# 2_FPGA.net
KiCad netlist of a schematic drawn in Altium Designer
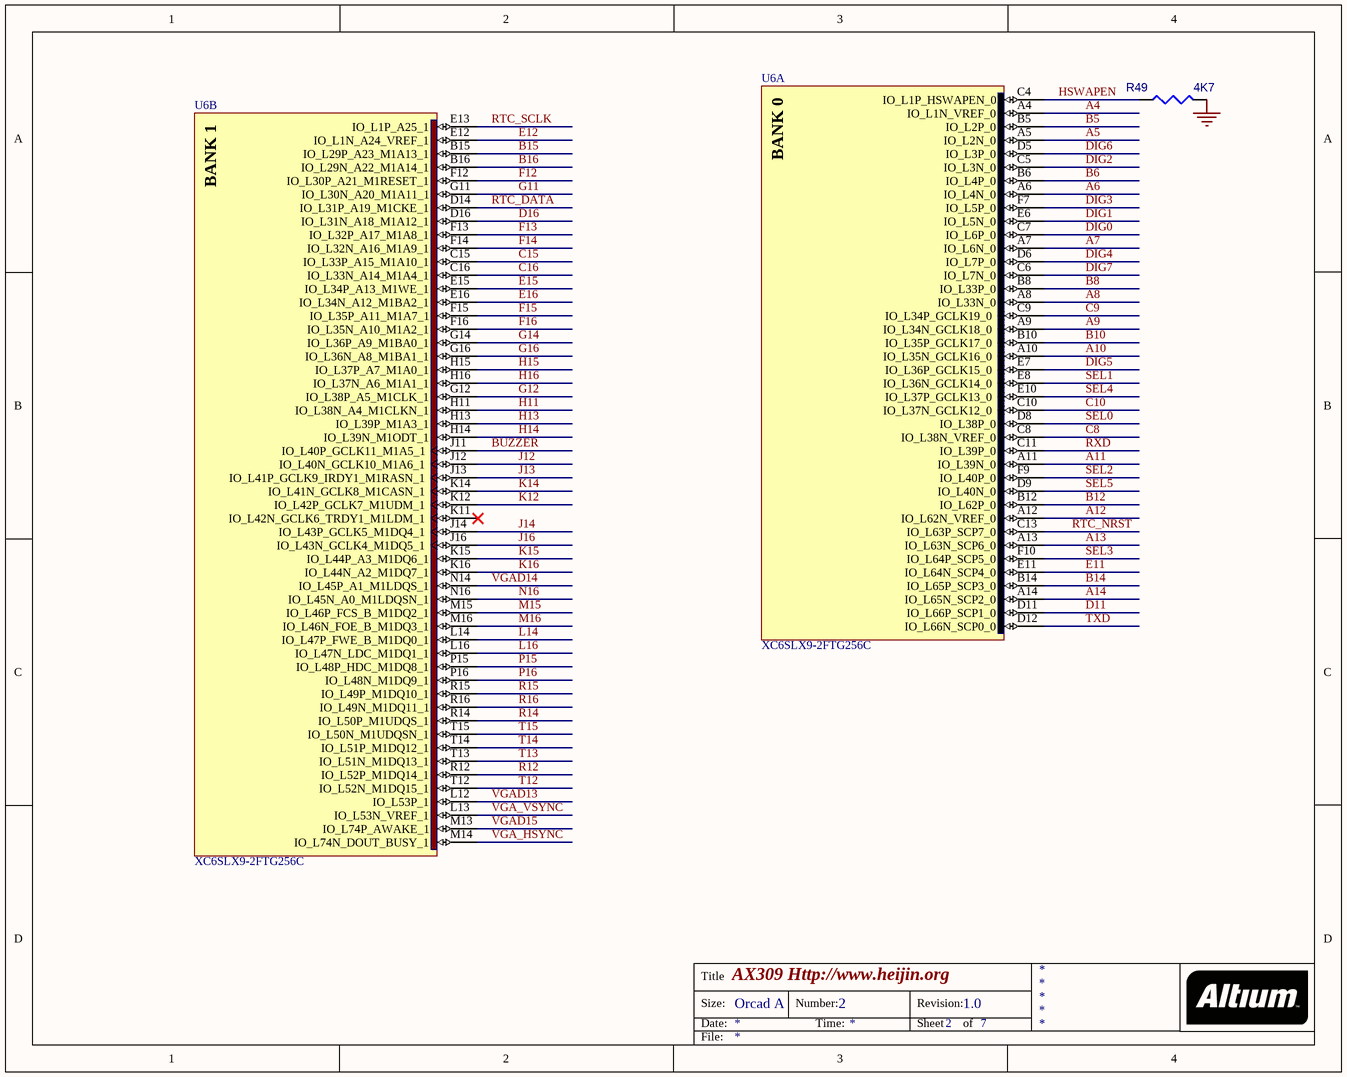
[diagram p0: 2_FPGA.SchDoc]

(export (version "E")
  (design (tool "Eeschema 10.0.6"))
  (components
    (comp (ref "R49") (value "4K7") (footprint "0603") (libsource (lib "*") (part "R")))
    (comp (ref "U6")
      (value "XC6SLX9-2FTG256C")
      (footprint "FTG256")
      (libsource (lib "Xilinx Spartan-6") (part "XC6SLX9-2FTG256C"))
    )
  )
  (nets
    (net (code "1") (name "/A4") (class "Default")
      (node (ref "U6") (pin "A4") (pinfunction "IO_L1N_VREF_0_A4") (pintype "bidirectional"))
    )
    (net (code "2") (name "/A5") (class "Default")
      (node (ref "U6") (pin "A5") (pinfunction "IO_L2N_0_A5") (pintype "bidirectional"))
    )
    (net (code "3") (name "/A6") (class "Default")
      (node (ref "U6") (pin "A6") (pinfunction "IO_L4N_0_A6") (pintype "bidirectional"))
    )
    (net (code "4") (name "/A7") (class "Default")
      (node (ref "U6") (pin "A7") (pinfunction "IO_L6N_0_A7") (pintype "bidirectional"))
    )
    (net (code "5") (name "/A8") (class "Default")
      (node (ref "U6") (pin "A8") (pinfunction "IO_L33N_0_A8") (pintype "bidirectional"))
    )
    (net (code "6") (name "/A9") (class "Default")
      (node (ref "U6") (pin "A9") (pinfunction "IO_L34N_GCLK18_0_A9") (pintype "bidirectional"))
    )
    (net (code "7") (name "/A10") (class "Default")
      (node (ref "U6") (pin "A10") (pinfunction "IO_L35N_GCLK16_0_A10") (pintype "bidirectional"))
    )
    (net (code "8") (name "/A11") (class "Default")
      (node (ref "U6") (pin "A11") (pinfunction "IO_L39N_0_A11") (pintype "bidirectional"))
    )
    (net (code "9") (name "/A12") (class "Default")
      (node (ref "U6") (pin "A12") (pinfunction "IO_L62N_VREF_0_A12") (pintype "bidirectional"))
    )
    (net (code "10") (name "/A13") (class "Default")
      (node (ref "U6") (pin "A13") (pinfunction "IO_L63N_SCP6_0_A13") (pintype "bidirectional"))
    )
    (net (code "11") (name "/A14") (class "Default")
      (node (ref "U6") (pin "A14") (pinfunction "IO_L65N_SCP2_0_A14") (pintype "bidirectional"))
    )
    (net (code "12") (name "/B5") (class "Default")
      (node (ref "U6") (pin "B5") (pinfunction "IO_L2P_0_B5") (pintype "bidirectional"))
    )
    (net (code "13") (name "/B6") (class "Default")
      (node (ref "U6") (pin "B6") (pinfunction "IO_L4P_0_B6") (pintype "bidirectional"))
    )
    (net (code "14") (name "/B8") (class "Default")
      (node (ref "U6") (pin "B8") (pinfunction "IO_L33P_0_B8") (pintype "bidirectional"))
    )
    (net (code "15") (name "/B10") (class "Default")
      (node (ref "U6") (pin "B10") (pinfunction "IO_L35P_GCLK17_0_B10") (pintype "bidirectional"))
    )
    (net (code "16") (name "/B12") (class "Default")
      (node (ref "U6") (pin "B12") (pinfunction "IO_L62P_0_B12") (pintype "bidirectional"))
    )
    (net (code "17") (name "/B14") (class "Default")
      (node (ref "U6") (pin "B14") (pinfunction "IO_L65P_SCP3_0_B14") (pintype "bidirectional"))
    )
    (net (code "18") (name "/B15") (class "Default")
      (node (ref "U6") (pin "B15") (pinfunction "IO_L29P_A23_M1A13_1_B15") (pintype "bidirectional"))
    )
    (net (code "19") (name "/B16") (class "Default")
      (node (ref "U6") (pin "B16") (pinfunction "IO_L29N_A22_M1A14_1_B16") (pintype "bidirectional"))
    )
    (net (code "20") (name "/BUZZER") (class "Default")
      (node (ref "U6") (pin "J11") (pinfunction "IO_L40P_GCLK11_M1A5_1_J11") (pintype "bidirectional"))
    )
    (net (code "21") (name "/C8") (class "Default")
      (node (ref "U6") (pin "C8") (pinfunction "IO_L38N_VREF_0_C8") (pintype "bidirectional"))
    )
    (net (code "22") (name "/C9") (class "Default")
      (node (ref "U6") (pin "C9") (pinfunction "IO_L34P_GCLK19_0_C9") (pintype "bidirectional"))
    )
    (net (code "23") (name "/C10") (class "Default")
      (node (ref "U6") (pin "C10") (pinfunction "IO_L37N_GCLK12_0_C10") (pintype "bidirectional"))
    )
    (net (code "24") (name "/C15") (class "Default")
      (node (ref "U6") (pin "C15") (pinfunction "IO_L33P_A15_M1A10_1_C15") (pintype "bidirectional"))
    )
    (net (code "25") (name "/C16") (class "Default")
      (node (ref "U6") (pin "C16") (pinfunction "IO_L33N_A14_M1A4_1_C16") (pintype "bidirectional"))
    )
    (net (code "26") (name "/D11") (class "Default")
      (node (ref "U6") (pin "D11") (pinfunction "IO_L66P_SCP1_0_D11") (pintype "bidirectional"))
    )
    (net (code "27") (name "/D16") (class "Default")
      (node (ref "U6") (pin "D16") (pinfunction "IO_L31N_A18_M1A12_1_D16") (pintype "bidirectional"))
    )
    (net (code "28") (name "/DIG0") (class "Default")
      (node (ref "U6") (pin "C7") (pinfunction "IO_L6P_0_C7") (pintype "bidirectional"))
    )
    (net (code "29") (name "/DIG1") (class "Default")
      (node (ref "U6") (pin "E6") (pinfunction "IO_L5N_0_E6") (pintype "bidirectional"))
    )
    (net (code "30") (name "/DIG2") (class "Default")
      (node (ref "U6") (pin "C5") (pinfunction "IO_L3N_0_C5") (pintype "bidirectional"))
    )
    (net (code "31") (name "/DIG3") (class "Default")
      (node (ref "U6") (pin "F7") (pinfunction "IO_L5P_0_F7") (pintype "bidirectional"))
    )
    (net (code "32") (name "/DIG4") (class "Default")
      (node (ref "U6") (pin "D6") (pinfunction "IO_L7P_0_D6") (pintype "bidirectional"))
    )
    (net (code "33") (name "/DIG5") (class "Default")
      (node (ref "U6") (pin "E7") (pinfunction "IO_L36P_GCLK15_0_E7") (pintype "bidirectional"))
    )
    (net (code "34") (name "/DIG6") (class "Default")
      (node (ref "U6") (pin "D5") (pinfunction "IO_L3P_0_D5") (pintype "bidirectional"))
    )
    (net (code "35") (name "/DIG7") (class "Default")
      (node (ref "U6") (pin "C6") (pinfunction "IO_L7N_0_C6") (pintype "bidirectional"))
    )
    (net (code "36") (name "/E11") (class "Default")
      (node (ref "U6") (pin "E11") (pinfunction "IO_L64N_SCP4_0_E11") (pintype "bidirectional"))
    )
    (net (code "37") (name "/E12") (class "Default")
      (node (ref "U6") (pin "E12") (pinfunction "IO_L1N_A24_VREF_1_E12") (pintype "bidirectional"))
    )
    (net (code "38") (name "/E15") (class "Default")
      (node (ref "U6") (pin "E15") (pinfunction "IO_L34P_A13_M1WE_1_E15") (pintype "bidirectional"))
    )
    (net (code "39") (name "/E16") (class "Default")
      (node (ref "U6") (pin "E16") (pinfunction "IO_L34N_A12_M1BA2_1_E16") (pintype "bidirectional"))
    )
    (net (code "40") (name "/F12") (class "Default")
      (node (ref "U6") (pin "F12") (pinfunction "IO_L30P_A21_M1RESET_1_F12") (pintype "bidirectional"))
    )
    (net (code "41") (name "/F13") (class "Default")
      (node (ref "U6") (pin "F13") (pinfunction "IO_L32P_A17_M1A8_1_F13") (pintype "bidirectional"))
    )
    (net (code "42") (name "/F14") (class "Default")
      (node (ref "U6") (pin "F14") (pinfunction "IO_L32N_A16_M1A9_1_F14") (pintype "bidirectional"))
    )
    (net (code "43") (name "/F15") (class "Default")
      (node (ref "U6") (pin "F15") (pinfunction "IO_L35P_A11_M1A7_1_F15") (pintype "bidirectional"))
    )
    (net (code "44") (name "/F16") (class "Default")
      (node (ref "U6") (pin "F16") (pinfunction "IO_L35N_A10_M1A2_1_F16") (pintype "bidirectional"))
    )
    (net (code "45") (name "/G11") (class "Default")
      (node (ref "U6") (pin "G11") (pinfunction "IO_L30N_A20_M1A11_1_G11") (pintype "bidirectional"))
    )
    (net (code "46") (name "/G12") (class "Default")
      (node (ref "U6") (pin "G12") (pinfunction "IO_L38P_A5_M1CLK_1_G12") (pintype "bidirectional"))
    )
    (net (code "47") (name "/G14") (class "Default")
      (node (ref "U6") (pin "G14") (pinfunction "IO_L36P_A9_M1BA0_1_G14") (pintype "bidirectional"))
    )
    (net (code "48") (name "/G16") (class "Default")
      (node (ref "U6") (pin "G16") (pinfunction "IO_L36N_A8_M1BA1_1_G16") (pintype "bidirectional"))
    )
    (net (code "49") (name "/H11") (class "Default")
      (node (ref "U6") (pin "H11") (pinfunction "IO_L38N_A4_M1CLKN_1_H11") (pintype "bidirectional"))
    )
    (net (code "50") (name "/H13") (class "Default")
      (node (ref "U6") (pin "H13") (pinfunction "IO_L39P_M1A3_1_H13") (pintype "bidirectional"))
    )
    (net (code "51") (name "/H14") (class "Default")
      (node (ref "U6") (pin "H14") (pinfunction "IO_L39N_M1ODT_1_H14") (pintype "bidirectional"))
    )
    (net (code "52") (name "/H15") (class "Default")
      (node (ref "U6") (pin "H15") (pinfunction "IO_L37P_A7_M1A0_1_H15") (pintype "bidirectional"))
    )
    (net (code "53") (name "/H16") (class "Default")
      (node (ref "U6") (pin "H16") (pinfunction "IO_L37N_A6_M1A1_1_H16") (pintype "bidirectional"))
    )
    (net (code "54") (name "/HSWAPEN") (class "Default")
      (node (ref "R49") (pin "1") (pinfunction "1_1") (pintype "passive"))
      (node (ref "U6") (pin "C4") (pinfunction "IO_L1P_HSWAPEN_0_C4") (pintype "bidirectional"))
    )
    (net (code "55") (name "/J12") (class "Default")
      (node (ref "U6") (pin "J12") (pinfunction "IO_L40N_GCLK10_M1A6_1_J12") (pintype "bidirectional"))
    )
    (net (code "56") (name "/J13") (class "Default")
      (node (ref "U6") (pin "J13") (pinfunction "IO_L41P_GCLK9_IRDY1_M1RASN_1_J13") (pintype "bidirectional"))
    )
    (net (code "57") (name "/J14") (class "Default")
      (node (ref "U6") (pin "J14") (pinfunction "IO_L43P_GCLK5_M1DQ4_1_J14") (pintype "bidirectional"))
    )
    (net (code "58") (name "/J16") (class "Default")
      (node (ref "U6") (pin "J16") (pinfunction "IO_L43N_GCLK4_M1DQ5_1_J16") (pintype "bidirectional"))
    )
    (net (code "59") (name "/K12") (class "Default")
      (node (ref "U6") (pin "K12") (pinfunction "IO_L42P_GCLK7_M1UDM_1_K12") (pintype "bidirectional"))
    )
    (net (code "60") (name "/K14") (class "Default")
      (node (ref "U6") (pin "K14") (pinfunction "IO_L41N_GCLK8_M1CASN_1_K14") (pintype "bidirectional"))
    )
    (net (code "61") (name "/K15") (class "Default")
      (node (ref "U6") (pin "K15") (pinfunction "IO_L44P_A3_M1DQ6_1_K15") (pintype "bidirectional"))
    )
    (net (code "62") (name "/K16") (class "Default")
      (node (ref "U6") (pin "K16") (pinfunction "IO_L44N_A2_M1DQ7_1_K16") (pintype "bidirectional"))
    )
    (net (code "63") (name "/L14") (class "Default")
      (node (ref "U6") (pin "L14") (pinfunction "IO_L47P_FWE_B_M1DQ0_1_L14") (pintype "bidirectional"))
    )
    (net (code "64") (name "/L16") (class "Default")
      (node (ref "U6") (pin "L16") (pinfunction "IO_L47N_LDC_M1DQ1_1_L16") (pintype "bidirectional"))
    )
    (net (code "65") (name "/M15") (class "Default")
      (node (ref "U6") (pin "M15") (pinfunction "IO_L46P_FCS_B_M1DQ2_1_M15") (pintype "bidirectional"))
    )
    (net (code "66") (name "/M16") (class "Default")
      (node (ref "U6") (pin "M16") (pinfunction "IO_L46N_FOE_B_M1DQ3_1_M16") (pintype "bidirectional"))
    )
    (net (code "67") (name "/N16") (class "Default")
      (node (ref "U6") (pin "N16") (pinfunction "IO_L45N_A0_M1LDQSN_1_N16") (pintype "bidirectional"))
    )
    (net (code "68") (name "/P15") (class "Default")
      (node (ref "U6") (pin "P15") (pinfunction "IO_L48P_HDC_M1DQ8_1_P15") (pintype "bidirectional"))
    )
    (net (code "69") (name "/P16") (class "Default")
      (node (ref "U6") (pin "P16") (pinfunction "IO_L48N_M1DQ9_1_P16") (pintype "bidirectional"))
    )
    (net (code "70") (name "/R12") (class "Default")
      (node (ref "U6") (pin "R12") (pinfunction "IO_L52P_M1DQ14_1_R12") (pintype "bidirectional"))
    )
    (net (code "71") (name "/R14") (class "Default")
      (node (ref "U6") (pin "R14") (pinfunction "IO_L50P_M1UDQS_1_R14") (pintype "bidirectional"))
    )
    (net (code "72") (name "/R15") (class "Default")
      (node (ref "U6") (pin "R15") (pinfunction "IO_L49P_M1DQ10_1_R15") (pintype "bidirectional"))
    )
    (net (code "73") (name "/R16") (class "Default")
      (node (ref "U6") (pin "R16") (pinfunction "IO_L49N_M1DQ11_1_R16") (pintype "bidirectional"))
    )
    (net (code "74") (name "/RTC_DATA") (class "Default")
      (node (ref "U6") (pin "D14") (pinfunction "IO_L31P_A19_M1CKE_1_D14") (pintype "bidirectional"))
    )
    (net (code "75") (name "/RTC_NRST") (class "Default")
      (node (ref "U6") (pin "C13") (pinfunction "IO_L63P_SCP7_0_C13") (pintype "bidirectional"))
    )
    (net (code "76") (name "/RTC_SCLK") (class "Default")
      (node (ref "U6") (pin "E13") (pinfunction "IO_L1P_A25_1_E13") (pintype "bidirectional"))
    )
    (net (code "77") (name "/RXD") (class "Default")
      (node (ref "U6") (pin "C11") (pinfunction "IO_L39P_0_C11") (pintype "bidirectional"))
    )
    (net (code "78") (name "/SEL0") (class "Default")
      (node (ref "U6") (pin "D8") (pinfunction "IO_L38P_0_D8") (pintype "bidirectional"))
    )
    (net (code "79") (name "/SEL1") (class "Default")
      (node (ref "U6") (pin "E8") (pinfunction "IO_L36N_GCLK14_0_E8") (pintype "bidirectional"))
    )
    (net (code "80") (name "/SEL2") (class "Default")
      (node (ref "U6") (pin "F9") (pinfunction "IO_L40P_0_F9") (pintype "bidirectional"))
    )
    (net (code "81") (name "/SEL3") (class "Default")
      (node (ref "U6") (pin "F10") (pinfunction "IO_L64P_SCP5_0_F10") (pintype "bidirectional"))
    )
    (net (code "82") (name "/SEL4") (class "Default")
      (node (ref "U6") (pin "E10") (pinfunction "IO_L37P_GCLK13_0_E10") (pintype "bidirectional"))
    )
    (net (code "83") (name "/SEL5") (class "Default")
      (node (ref "U6") (pin "D9") (pinfunction "IO_L40N_0_D9") (pintype "bidirectional"))
    )
    (net (code "84") (name "/T12") (class "Default")
      (node (ref "U6") (pin "T12") (pinfunction "IO_L52N_M1DQ15_1_T12") (pintype "bidirectional"))
    )
    (net (code "85") (name "/T13") (class "Default")
      (node (ref "U6") (pin "T13") (pinfunction "IO_L51N_M1DQ13_1_T13") (pintype "bidirectional"))
    )
    (net (code "86") (name "/T14") (class "Default")
      (node (ref "U6") (pin "T14") (pinfunction "IO_L51P_M1DQ12_1_T14") (pintype "bidirectional"))
    )
    (net (code "87") (name "/T15") (class "Default")
      (node (ref "U6") (pin "T15") (pinfunction "IO_L50N_M1UDQSN_1_T15") (pintype "bidirectional"))
    )
    (net (code "88") (name "/TXD") (class "Default")
      (node (ref "U6") (pin "D12") (pinfunction "IO_L66N_SCP0_0_D12") (pintype "bidirectional"))
    )
    (net (code "89") (name "/VGAD13") (class "Default")
      (node (ref "U6") (pin "L12") (pinfunction "IO_L53P_1_L12") (pintype "bidirectional"))
    )
    (net (code "90") (name "/VGAD14") (class "Default")
      (node (ref "U6") (pin "N14") (pinfunction "IO_L45P_A1_M1LDQS_1_N14") (pintype "bidirectional"))
    )
    (net (code "91") (name "/VGAD15") (class "Default")
      (node (ref "U6") (pin "M13") (pinfunction "IO_L74P_AWAKE_1_M13") (pintype "bidirectional"))
    )
    (net (code "92") (name "/VGA_HSYNC") (class "Default")
      (node (ref "U6") (pin "M14") (pinfunction "IO_L74N_DOUT_BUSY_1_M14") (pintype "bidirectional"))
    )
    (net (code "93") (name "/VGA_VSYNC") (class "Default")
      (node (ref "U6") (pin "L13") (pinfunction "IO_L53N_VREF_1_L13") (pintype "bidirectional"))
    )
    (net (code "94") (name "GND") (class "Default")
      (node (ref "R49") (pin "2") (pinfunction "2_2") (pintype "passive"))
    )
    (net (code "95") (name "unconnected-(U6B-IO_L42N_GCLK6_TRDY1_M1LDM_1-PadK11)") (class "Default")
      (node (ref "U6") (pin "K11") (pinfunction "IO_L42N_GCLK6_TRDY1_M1LDM_1_K11") (pintype "bidirectional+no_connect"))
    )
  )
)
